# Power_Management.net
KiCad netlist of a schematic drawn in Altium Designer
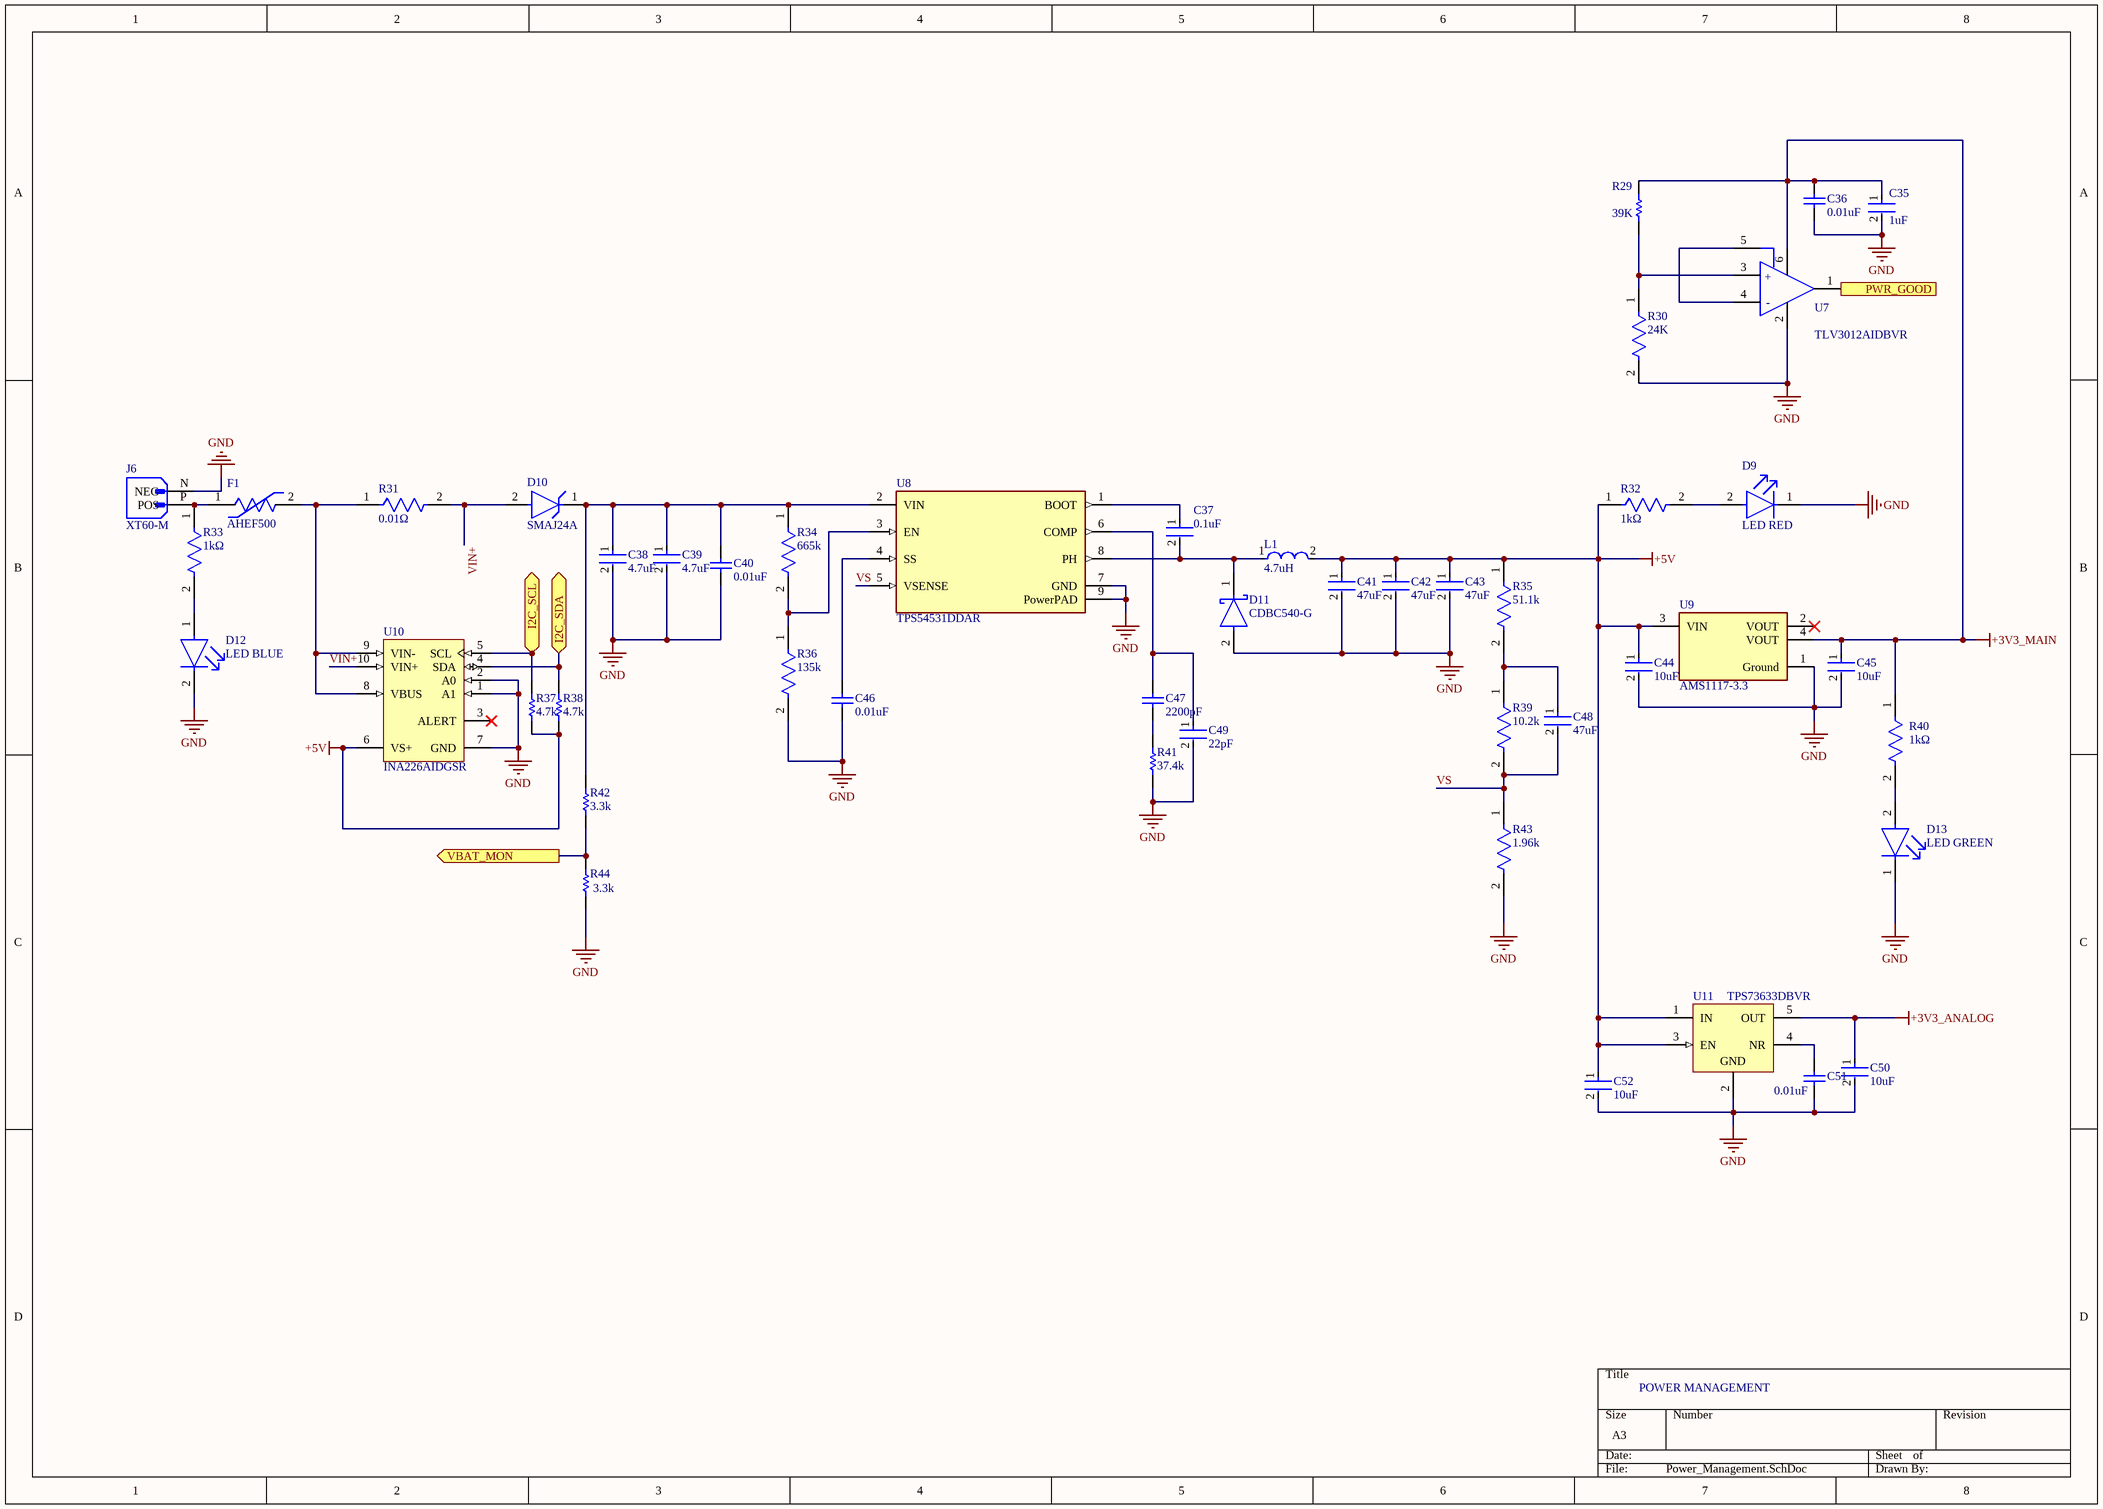
[diagram p0: Power_Management.SchDoc]

(export (version "E")
  (design (tool "Eeschema 10.0.6"))
  (components
    (comp (ref "C35")
      (value "1uF")
      (footprint "FP-GCJ21B-0_3-IPC_B")
      (description "Multilayer Ceramic Capacitors MLCC - SMD/SMT 0805 1uF 10%, 16VDC,  X8L +15/-40%")
      (libsource (lib "Altium Content Vault") (part "02cd4be3c70576c341d710602a673aa"))
    )
    (comp (ref "C36")
      (value "0.01uF")
      (footprint "CAPC1608X87X35NL15T15")
      (fields (field (name "PART NUMBER") "C0603S103J5RACTU") (field (name "MANUFACTURER") "Kemet"))
      (libsource (lib "Altium Content Vault") (part "CAP"))
    )
    (comp (ref "C37")
      (value "0.1uF")
      (footprint "FP-0805B-IPC_C")
      (description "CAP CER 0.1UF 50V X7R 0805")
      (fields (field (name "VOLTAGE") "50V") (field (name "TOLERANCE") "10%"))
      (libsource (lib "Altium Content Vault") (part "02cd4be3c70576c341d710602a673aa"))
    )
    (comp (ref "C38")
      (value "4.7uF")
      (footprint "FP-CC0603-DA-MFG")
      (description "CAP CER 4.7UF 25V X5R 0603")
      (fields
        (field (name "MANUFACTURER") "YAGEO")
        (field (name "MANUFACTURER PART NUMBER") "CC0603KRX5R8BB475")
      )
      (libsource (lib "Altium Content Vault") (part "11868f565c42a9108669ba33697ecf6"))
    )
    (comp (ref "C39")
      (value "4.7uF")
      (footprint "FP-CC0603-DA-MFG")
      (description "CAP CER 4.7UF 25V X5R 0603")
      (fields
        (field (name "MANUFACTURER") "YAGEO")
        (field (name "MANUFACTURER PART NUMBER") "CC0603KRX5R8BB475")
      )
      (libsource (lib "Altium Content Vault") (part "11868f565c42a9108669ba33697ecf6"))
    )
    (comp (ref "C40")
      (value "0.01uF")
      (footprint "CAPC1608X87X35NL15T15")
      (fields (field (name "PART NUMBER") "C0603S103J5RACTU") (field (name "MANUFACTURER") "Kemet"))
      (libsource (lib "Altium Content Vault") (part "CAP"))
    )
    (comp (ref "C41")
      (value "47uF")
      (footprint "FP-0603-L_1_6_0_2-W_0_8_0-MFG")
      (description "Multilayer Ceramic Capacitor 47uF 4V X6S 20% SMD 0603 T/R")
      (libsource (lib "Altium Content Vault") (part "b4654b650e69147ec39a6b967a45e02"))
    )
    (comp (ref "C42")
      (value "47uF")
      (footprint "FP-0603-L_1_6_0_2-W_0_8_0-MFG")
      (description "Multilayer Ceramic Capacitor 47uF 4V X6S 20% SMD 0603 T/R")
      (libsource (lib "Altium Content Vault") (part "b4654b650e69147ec39a6b967a45e02"))
    )
    (comp (ref "C43")
      (value "47uF")
      (footprint "FP-0603-L_1_6_0_2-W_0_8_0-MFG")
      (description "Multilayer Ceramic Capacitor 47uF 4V X6S 20% SMD 0603 T/R")
      (libsource (lib "Altium Content Vault") (part "b4654b650e69147ec39a6b967a45e02"))
    )
    (comp (ref "C44")
      (value "10uF")
      (footprint "FP-C0603C106M8PACTU-MFG")
      (description "CAP CER 10UF 10V X5R 0603")
      (libsource (lib "Altium Content Vault") (part "02cd4be3c70576c341d710602a673aa"))
    )
    (comp (ref "C45")
      (value "10uF")
      (footprint "FP-C0603C106M8PACTU-MFG")
      (description "CAP CER 10UF 10V X5R 0603")
      (libsource (lib "Altium Content Vault") (part "02cd4be3c70576c341d710602a673aa"))
    )
    (comp (ref "C46")
      (value "0.01uF")
      (footprint "CAPC1608X87X35NL15T15")
      (fields (field (name "PART NUMBER") "C0603S103J5RACTU") (field (name "MANUFACTURER") "Kemet"))
      (libsource (lib "Altium Content Vault") (part "CAP"))
    )
    (comp (ref "C47")
      (value "2200pF")
      (footprint "CAPC1608X90X35NL15T15")
      (fields
        (field (name "MANUFACTURER") "AVX Interconnect / Elco")
        (field (name "PART NUMBER") "06035C222KAZ2A")
      )
      (libsource (lib "Altium Content Vault") (part "CAP"))
    )
    (comp (ref "C48")
      (value "47uF")
      (footprint "FP-0603-L_1_6_0_2-W_0_8_0-MFG")
      (description "Multilayer Ceramic Capacitor 47uF 4V X6S 20% SMD 0603 T/R")
      (libsource (lib "Altium Content Vault") (part "b4654b650e69147ec39a6b967a45e02"))
    )
    (comp (ref "C49")
      (value "22pF")
      (footprint "FP-C0603C-CF-MFG")
      (description "CAP CER 22PF 100V C0G/NP0 0603")
      (fields
        (field (name "MANUFACTURER") "KEMET")
        (field (name "MANUFACTURER PART NUMBER") "C0603C220J1GACAUTO")
      )
      (libsource (lib "Altium Content Vault") (part "b4654b650e69147ec39a6b967a45e02"))
    )
    (comp (ref "C50")
      (value "10uF")
      (footprint "FP-C0805C106K8RACAUTO-MFG")
      (description "CAP CER 10UF 10V X7R 0805")
      (fields (field (name "TOLERANCE") "10%"))
      (libsource (lib "Altium Content Vault") (part "b4654b650e69147ec39a6b967a45e02"))
    )
    (comp (ref "C51")
      (value "0.01uF")
      (footprint "CAPC1608X87X35NL15T15")
      (fields (field (name "PART NUMBER") "C0603S103J5RACTU") (field (name "MANUFACTURER") "Kemet"))
      (libsource (lib "Altium Content Vault") (part "CAP"))
    )
    (comp (ref "C52")
      (value "10uF")
      (footprint "FP-C0805C106K8RACAUTO-MFG")
      (description "CAP CER 10UF 10V X7R 0805")
      (fields (field (name "TOLERANCE") "10%"))
      (libsource (lib "Altium Content Vault") (part "b4654b650e69147ec39a6b967a45e02"))
    )
    (comp (ref "D9")
      (value "LED RED")
      (footprint "FP-SML-LXT0805IW-TR-MFG")
      (description "LED RED DIFFUSED SMD")
      (libsource (lib "Altium Content Vault") (part "8706943c75ba83719d021d2fdc84c58"))
    )
    (comp (ref "D10")
      (value "SMAJ24A")
      (footprint "FP-SMAJ-MFG")
      (description "TVS DIODE 24V 38.9V DO214AC")
      (fields
        (field (name "OCTOPART") "https://octopart.com/smaj24a-littelfuse-350003")
        (field (name "MANUFACTURER") "Littelfuse Inc")
      )
      (libsource (lib "Altium Content Vault") (part "f813f71cba58e380607f5dd3caf9714"))
    )
    (comp (ref "D11")
      (value "CDBC540-G")
      (footprint "FP-DO-214AB_SMC-MFG")
      (description "DIODE SCHOTTKY 40V 5A DO214AB")
      (libsource (lib "Altium Content Vault") (part "1d6ec82d83fb6aee721767c19dac4b9"))
    )
    (comp (ref "D12")
      (value "LED BLUE")
      (footprint "FP-SM0805UBWC-MFG")
      (description "LED BLUE CLEAR 0805 SMD")
      (libsource (lib "Altium Content Vault") (part "ab1c01a81903e929fc6c44469aada92"))
    )
    (comp (ref "D13")
      (value "LED GREEN")
      (footprint "FP-LTST-C171GKT-MFG")
      (description "LED GREEN CLEAR CHIP SMD")
      (libsource (lib "Altium Content Vault") (part "8706943c75ba83719d021d2fdc84c58"))
    )
    (comp (ref "F1")
      (value "AHEF500")
      (footprint "FP-AHEF500-MFG")
      (description "PTC RESET FUSE 32V 5A RADIAL")
      (fields
        (field (name "OCTOPART") "https://octopart.com/ahef500-littelfuse-74214520")
        (field (name "MANUFACTURER") "Littelfuse Inc.")
      )
      (libsource (lib "Altium Content Vault") (part "fdf083d5f6389a9a1c4e51137f46658"))
    )
    (comp (ref "J6")
      (value "XT60-M")
      (footprint "AMASS_XT60-M")
      (description "Plug; DC supply; XT60; male; PIN: 2; for cable; soldered; 30A; 500V")
      (fields (field (name "MF") "AMASS"))
      (libsource (lib "XT60-M") (part "XT60-M"))
    )
    (comp (ref "L1")
      (value "4.7uH")
      (footprint "FP-MLZ1608-IPC_A")
      (description "Shielded Multilayer Inductor 4.7uH ±20% 350mA 650mΩ SMD 0603")
      (fields (field (name "TOLERANCE") "20%"))
      (libsource (lib "Altium Content Vault") (part "725321dda6339637d4d059423bc1c3c"))
    )
    (comp (ref "R29")
      (value "39K")
      (footprint "RESC0603(1608)_L")
      (description "39K 0.1W 5% 0603 (1608 Metric)  SMD")
      (fields (field (name "TOLERANCE") "5 %") (field (name "POWER") "0.1 W"))
      (libsource (lib "Altium Content Vault") (part "RES"))
    )
    (comp (ref "R30")
      (value "24K")
      (footprint "FP-CRCW0603-Pe3-MFG")
      (description "RES Thick Film, 24kΩ, 0.5%, 0.1W, 50ppm/°C, 0603")
      (fields (field (name "TOLERANCE") "0.5%"))
      (libsource (lib "Altium Content Vault") (part "1029c3af85768c4190bb7ad29bc67b5"))
    )
    (comp (ref "R31")
      (value "0.01Ω")
      (footprint "FP-GMR320-MFG")
      (description "RES 10M OHM 1% 10W 2817")
      (libsource (lib "Altium Content Vault") (part "1029c3af85768c4190bb7ad29bc67b5"))
    )
    (comp (ref "R32")
      (value "1kΩ")
      (footprint "FP-RNCF0603-MFG")
      (description "RES 1K OHM, 0.01%, 2 PPM, 0.1W,")
      (libsource (lib "Altium Content Vault") (part "1029c3af85768c4190bb7ad29bc67b5"))
    )
    (comp (ref "R33")
      (value "1kΩ")
      (footprint "FP-RNCF0603-MFG")
      (description "RES 1K OHM, 0.01%, 2 PPM, 0.1W,")
      (libsource (lib "Altium Content Vault") (part "1029c3af85768c4190bb7ad29bc67b5"))
    )
    (comp (ref "R34")
      (value "665k")
      (footprint "FP-CRCW0603-HPe3-IPC_B")
      (description "RES Thick Film, 665kΩ, 1%, 0.33W, 100ppm/°C, 0603")
      (fields (field (name "TOLERANCE") "1%"))
      (libsource (lib "Altium Content Vault") (part "1029c3af85768c4190bb7ad29bc67b5"))
    )
    (comp (ref "R35")
      (value "51.1k")
      (footprint "FP-CRCW0603-e3-IPC_B")
      (description "RES Thick Film, 511kΩ, 1%, 0.1W, 100ppm/°C, 0603")
      (fields (field (name "TOLERANCE") "1%"))
      (libsource (lib "Altium Content Vault") (part "1029c3af85768c4190bb7ad29bc67b5"))
    )
    (comp (ref "R36")
      (value "135k")
      (footprint "FP-CRCW0603-e3-IPC_C")
      (description "RES Thick Film, 130kΩ, 5%, 0.1W, 200ppm/°C, 0603")
      (fields (field (name "TOLERANCE") "5%"))
      (libsource (lib "Altium Content Vault") (part "1029c3af85768c4190bb7ad29bc67b5"))
    )
    (comp (ref "R37")
      (value "4.7k")
      (footprint "RESC3225X75X50ML15T25")
      (fields (field (name "MANUFACTURER") "Vishay Dale") (field (name "PART NUMBER") "TNPW12104K70BETA"))
      (libsource (lib "Altium Content Vault") (part "RES"))
    )
    (comp (ref "R38")
      (value "4.7k")
      (footprint "RESC3225X75X50ML15T25")
      (fields (field (name "MANUFACTURER") "Vishay Dale") (field (name "PART NUMBER") "TNPW12104K70BETA"))
      (libsource (lib "Altium Content Vault") (part "RES"))
    )
    (comp (ref "R39")
      (value "10.2k")
      (footprint "FP-AC0603-IPC_B")
      (description "RES 2kΩ 1.00% 0.1W 0603")
      (fields (field (name "TOLERANCE") "1%"))
      (libsource (lib "Altium Content Vault") (part "1029c3af85768c4190bb7ad29bc67b5"))
    )
    (comp (ref "R40")
      (value "1kΩ")
      (footprint "FP-RNCF0603-MFG")
      (description "RES 1K OHM, 0.01%, 2 PPM, 0.1W,")
      (libsource (lib "Altium Content Vault") (part "1029c3af85768c4190bb7ad29bc67b5"))
    )
    (comp (ref "R41")
      (value "37.4k")
      (footprint "RESC1608X55X25NL10T15")
      (fields (field (name "PART NUMBER") "RC0603FR-07374KL") (field (name "MANUFACTURER") "Yageo"))
      (libsource (lib "Altium Content Vault") (part "RES"))
    )
    (comp (ref "R42")
      (value "3.3k")
      (footprint "RESC1812(4532)_L")
      (description "10K 0.75W 1% 1812 (4532 Metric)  SMD")
      (fields (field (name "POWER") "0.75 W") (field (name "TOLERANCE") "1 %"))
      (libsource (lib "Altium Content Vault") (part "RES"))
    )
    (comp (ref "R43")
      (value "1.96k")
      (footprint "FP-CRCW0603-HPe3-IPC_B")
      (description "RES Thick Film, 1.96kΩ, 1%, 0.33W, 100ppm/°C, 0603")
      (fields (field (name "TOLERANCE") "1%"))
      (libsource (lib "Altium Content Vault") (part "1029c3af85768c4190bb7ad29bc67b5"))
    )
    (comp (ref "R44")
      (value "3.3k")
      (footprint "RESC2512(6432)_M")
      (description "3K3 1W 1% 2512 (6432 Metric)  SMD")
      (fields (field (name "TOLERANCE") "1 %") (field (name "POWER") "1 W"))
      (libsource (lib "Altium Content Vault") (part "RES"))
    )
    (comp (ref "U7")
      (value "TLV3012AIDBVR")
      (footprint "FP-DBV0006A-IPC_B")
      (description "IC COMPARATOR 1.8V W/REF SOT23-6")
      (libsource (lib "Altium Content Vault") (part "c4a04de7fcb83ef995881f343e5bdea"))
    )
    (comp (ref "U8")
      (value "TPS54531DDAR")
      (footprint "FP-DDA0008E-MFG")
      (description "IC REG BUCK ADJUSTABLE 5A 8SOPWR")
      (libsource (lib "Altium Content Vault") (part "0ba9c67d8848e7a3c062535a516a02c"))
    )
    (comp (ref "U9")
      (value "AMS1117-3.3")
      (footprint "FP-AMS1117-IPC_C")
      (description "LDO Voltage Regulators 1A, 3.3V")
      (fields
        (field (name "OCTOPART") "https://octopart.com/ams1117-3.3-advanced+monolithic+systems-25899300")
        (field (name "MANUFACTURER") "Advanced Monolithic Systems")
      )
      (libsource (lib "Altium Content Vault") (part "8bdbb5f8e77002000e30dd2845d0354"))
    )
    (comp (ref "U10")
      (value "INA226AIDGSR")
      (footprint "DGS0010A_L")
      (libsource (lib "Altium Content Vault") (part "TI-INA226DGS10"))
    )
    (comp (ref "U11")
      (value "TPS73633DBVR")
      (footprint "DBV0005A_L")
      (fields (field (name "MANUFACTURER") "Texas Instruments"))
      (libsource (lib "Altium Content Vault") (part "TI-TPS79NXX-YYSOT5"))
    )
  )
  (nets
    (net (code "1") (name "+3V3_ANALOG") (class "Default")
      (node (ref "C50") (pin "1") (pinfunction "1_1") (pintype "passive"))
      (node (ref "U11") (pin "5") (pinfunction "OUT_5") (pintype "power_in"))
    )
    (net (code "2") (name "+3V3_MAIN") (class "Default")
      (node (ref "C35") (pin "1") (pinfunction "1_1") (pintype "passive"))
      (node (ref "C36") (pin "2") (pinfunction "2_2") (pintype "passive"))
      (node (ref "C45") (pin "1") (pinfunction "1_1") (pintype "passive"))
      (node (ref "R29") (pin "2") (pinfunction "2_2") (pintype "passive"))
      (node (ref "R40") (pin "1") (pinfunction "1_1") (pintype "passive"))
      (node (ref "U7") (pin "6") (pinfunction "V+_6") (pintype "power_in"))
      (node (ref "U9") (pin "4") (pinfunction "VOUT_4") (pintype "passive"))
    )
    (net (code "3") (name "+5V") (class "Default")
      (node (ref "C41") (pin "1") (pinfunction "1_1") (pintype "passive"))
      (node (ref "C42") (pin "1") (pinfunction "1_1") (pintype "passive"))
      (node (ref "C43") (pin "1") (pinfunction "1_1") (pintype "passive"))
      (node (ref "C44") (pin "1") (pinfunction "1_1") (pintype "passive"))
      (node (ref "C52") (pin "1") (pinfunction "1_1") (pintype "passive"))
      (node (ref "L1") (pin "2") (pinfunction "2_2") (pintype "passive"))
      (node (ref "R32") (pin "1") (pinfunction "1_1") (pintype "passive"))
      (node (ref "R35") (pin "1") (pinfunction "1_1") (pintype "passive"))
      (node (ref "R37") (pin "1") (pinfunction "1_1") (pintype "passive"))
      (node (ref "R38") (pin "1") (pinfunction "1_1") (pintype "passive"))
      (node (ref "U10") (pin "6") (pinfunction "VS+_6") (pintype "power_in"))
      (node (ref "U11") (pin "1") (pinfunction "IN_1") (pintype "power_in"))
      (node (ref "U11") (pin "3") (pinfunction "EN_3") (pintype "input"))
      (node (ref "U9") (pin "3") (pinfunction "VIN_3") (pintype "power_in"))
    )
    (net (code "4") (name "/I2C_SCL") (class "Default")
      (node (ref "R37") (pin "2") (pinfunction "2_2") (pintype "passive"))
      (node (ref "U10") (pin "5") (pinfunction "SCL_5") (pintype "input"))
    )
    (net (code "5") (name "/I2C_SDA") (class "Default")
      (node (ref "R38") (pin "2") (pinfunction "2_2") (pintype "passive"))
      (node (ref "U10") (pin "4") (pinfunction "SDA_4") (pintype "bidirectional"))
    )
    (net (code "6") (name "/PWR_GOOD") (class "Default")
      (node (ref "U7") (pin "1") (pinfunction "OUT_1") (pintype "passive"))
    )
    (net (code "7") (name "/VBAT_MON") (class "Default")
      (node (ref "R42") (pin "1") (pinfunction "1_1") (pintype "passive"))
      (node (ref "R44") (pin "2") (pinfunction "2_2") (pintype "passive"))
    )
    (net (code "8") (name "/VIN+") (class "Default")
      (node (ref "D10") (pin "2") (pinfunction "A_2") (pintype "passive"))
      (node (ref "R31") (pin "2") (pinfunction "2_2") (pintype "passive"))
      (node (ref "U10") (pin "10") (pinfunction "VIN+_10") (pintype "input"))
    )
    (net (code "9") (name "/VS") (class "Default")
      (node (ref "C48") (pin "2") (pinfunction "2_2") (pintype "passive"))
      (node (ref "R39") (pin "2") (pinfunction "2_2") (pintype "passive"))
      (node (ref "R43") (pin "1") (pinfunction "1_1") (pintype "passive"))
      (node (ref "U8") (pin "5") (pinfunction "VSENSE_5") (pintype "input"))
    )
    (net (code "10") (name "GND") (class "Default")
      (node (ref "C35") (pin "2") (pinfunction "2_2") (pintype "passive"))
      (node (ref "C36") (pin "1") (pinfunction "1_1") (pintype "passive"))
      (node (ref "C38") (pin "2") (pinfunction "2_2") (pintype "passive"))
      (node (ref "C39") (pin "2") (pinfunction "2_2") (pintype "passive"))
      (node (ref "C40") (pin "1") (pinfunction "1_1") (pintype "passive"))
      (node (ref "C41") (pin "2") (pinfunction "2_2") (pintype "passive"))
      (node (ref "C42") (pin "2") (pinfunction "2_2") (pintype "passive"))
      (node (ref "C43") (pin "2") (pinfunction "2_2") (pintype "passive"))
      (node (ref "C44") (pin "2") (pinfunction "2_2") (pintype "passive"))
      (node (ref "C45") (pin "2") (pinfunction "2_2") (pintype "passive"))
      (node (ref "C46") (pin "1") (pinfunction "1_1") (pintype "passive"))
      (node (ref "C49") (pin "2") (pinfunction "2_2") (pintype "passive"))
      (node (ref "C50") (pin "2") (pinfunction "2_2") (pintype "passive"))
      (node (ref "C51") (pin "1") (pinfunction "1_1") (pintype "passive"))
      (node (ref "C52") (pin "2") (pinfunction "2_2") (pintype "passive"))
      (node (ref "D11") (pin "2") (pinfunction "A_2") (pintype "passive"))
      (node (ref "D12") (pin "2") (pinfunction "C_2") (pintype "passive"))
      (node (ref "D13") (pin "1") (pinfunction "C_1") (pintype "passive"))
      (node (ref "D9") (pin "1") (pinfunction "C_1") (pintype "passive"))
      (node (ref "J6") (pin "N") (pinfunction "NEG_N") (pintype "passive"))
      (node (ref "R30") (pin "2") (pinfunction "2_2") (pintype "passive"))
      (node (ref "R36") (pin "2") (pinfunction "2_2") (pintype "passive"))
      (node (ref "R41") (pin "1") (pinfunction "1_1") (pintype "passive"))
      (node (ref "R43") (pin "2") (pinfunction "2_2") (pintype "passive"))
      (node (ref "R44") (pin "1") (pinfunction "1_1") (pintype "passive"))
      (node (ref "U10") (pin "1") (pinfunction "A1_1") (pintype "input"))
      (node (ref "U10") (pin "2") (pinfunction "A0_2") (pintype "input"))
      (node (ref "U10") (pin "7") (pinfunction "GND_7") (pintype "power_in"))
      (node (ref "U11") (pin "2") (pinfunction "GND_2") (pintype "power_in"))
      (node (ref "U7") (pin "2") (pinfunction "V-_2") (pintype "power_in"))
      (node (ref "U8") (pin "7") (pinfunction "GND_7") (pintype "power_in"))
      (node (ref "U8") (pin "9") (pinfunction "PowerPAD_9") (pintype "power_in"))
      (node (ref "U9") (pin "1") (pinfunction "Ground_1") (pintype "power_in"))
    )
    (net (code "11") (name "Net-(C47-Pad1)") (class "Default")
      (node (ref "C47") (pin "1") (pinfunction "1_1") (pintype "passive"))
      (node (ref "R41") (pin "2") (pinfunction "2_2") (pintype "passive"))
    )
    (net (code "12") (name "Net-(C48-Pad1)") (class "Default")
      (node (ref "C48") (pin "1") (pinfunction "1_1") (pintype "passive"))
      (node (ref "R35") (pin "2") (pinfunction "2_2") (pintype "passive"))
      (node (ref "R39") (pin "1") (pinfunction "1_1") (pintype "passive"))
    )
    (net (code "13") (name "Net-(D9-A)") (class "Default")
      (node (ref "D9") (pin "2") (pinfunction "A_2") (pintype "passive"))
      (node (ref "R32") (pin "2") (pinfunction "2_2") (pintype "passive"))
    )
    (net (code "14") (name "Net-(D10-C)") (class "Default")
      (node (ref "C38") (pin "1") (pinfunction "1_1") (pintype "passive"))
      (node (ref "C39") (pin "1") (pinfunction "1_1") (pintype "passive"))
      (node (ref "C40") (pin "2") (pinfunction "2_2") (pintype "passive"))
      (node (ref "D10") (pin "1") (pinfunction "C_1") (pintype "passive"))
      (node (ref "R34") (pin "1") (pinfunction "1_1") (pintype "passive"))
      (node (ref "R42") (pin "2") (pinfunction "2_2") (pintype "passive"))
      (node (ref "U8") (pin "2") (pinfunction "VIN_2") (pintype "power_in"))
    )
    (net (code "15") (name "Net-(D11-C)") (class "Default")
      (node (ref "C37") (pin "2") (pinfunction "2_2") (pintype "passive"))
      (node (ref "D11") (pin "1") (pinfunction "C_1") (pintype "passive"))
      (node (ref "L1") (pin "1") (pinfunction "1_1") (pintype "passive"))
      (node (ref "U8") (pin "8") (pinfunction "PH_8") (pintype "output"))
    )
    (net (code "16") (name "Net-(D12-A)") (class "Default")
      (node (ref "D12") (pin "1") (pinfunction "A_1") (pintype "passive"))
      (node (ref "R33") (pin "2") (pinfunction "2_2") (pintype "passive"))
    )
    (net (code "17") (name "Net-(D13-A)") (class "Default")
      (node (ref "D13") (pin "2") (pinfunction "A_2") (pintype "passive"))
      (node (ref "R40") (pin "2") (pinfunction "2_2") (pintype "passive"))
    )
    (net (code "18") (name "Net-(J6-POS)") (class "Default")
      (node (ref "F1") (pin "1") (pinfunction "1_1") (pintype "passive"))
      (node (ref "J6") (pin "P") (pinfunction "POS_P") (pintype "passive"))
      (node (ref "R33") (pin "1") (pinfunction "1_1") (pintype "passive"))
    )
    (net (code "19") (name "Net-(U7-IN+)") (class "Default")
      (node (ref "R29") (pin "1") (pinfunction "1_1") (pintype "passive"))
      (node (ref "R30") (pin "1") (pinfunction "1_1") (pintype "passive"))
      (node (ref "U7") (pin "3") (pinfunction "IN+_3") (pintype "tri_state"))
    )
    (net (code "20") (name "Net-(U7-IN-)") (class "Default")
      (node (ref "U7") (pin "4") (pinfunction "IN-_4") (pintype "tri_state"))
      (node (ref "U7") (pin "5") (pinfunction "REF_5") (pintype "passive"))
    )
    (net (code "21") (name "Net-(U8-BOOT)") (class "Default")
      (node (ref "C37") (pin "1") (pinfunction "1_1") (pintype "passive"))
      (node (ref "U8") (pin "1") (pinfunction "BOOT_1") (pintype "output"))
    )
    (net (code "22") (name "Net-(U8-COMP)") (class "Default")
      (node (ref "C47") (pin "2") (pinfunction "2_2") (pintype "passive"))
      (node (ref "C49") (pin "1") (pinfunction "1_1") (pintype "passive"))
      (node (ref "U8") (pin "6") (pinfunction "COMP_6") (pintype "output"))
    )
    (net (code "23") (name "Net-(U8-EN)") (class "Default")
      (node (ref "R34") (pin "2") (pinfunction "2_2") (pintype "passive"))
      (node (ref "R36") (pin "1") (pinfunction "1_1") (pintype "passive"))
      (node (ref "U8") (pin "3") (pinfunction "EN_3") (pintype "input"))
    )
    (net (code "24") (name "Net-(U8-SS)") (class "Default")
      (node (ref "C46") (pin "2") (pinfunction "2_2") (pintype "passive"))
      (node (ref "U8") (pin "4") (pinfunction "SS_4") (pintype "input"))
    )
    (net (code "25") (name "Net-(U10-VBUS)") (class "Default")
      (node (ref "F1") (pin "2") (pinfunction "2_2") (pintype "passive"))
      (node (ref "R31") (pin "1") (pinfunction "1_1") (pintype "passive"))
      (node (ref "U10") (pin "8") (pinfunction "VBUS_8") (pintype "input"))
      (node (ref "U10") (pin "9") (pinfunction "VIN-_9") (pintype "input"))
    )
    (net (code "26") (name "Net-(U11-NR)") (class "Default")
      (node (ref "C51") (pin "2") (pinfunction "2_2") (pintype "passive"))
      (node (ref "U11") (pin "4") (pinfunction "NR_4") (pintype "passive"))
    )
    (net (code "27") (name "unconnected-(U9-VOUT-Pad2)") (class "Default")
      (node (ref "U9") (pin "2") (pinfunction "VOUT_2") (pintype "passive+no_connect"))
    )
    (net (code "28") (name "unconnected-(U10-ALERT-Pad3)") (class "Default")
      (node (ref "U10") (pin "3") (pinfunction "ALERT_3") (pintype "open_collector+no_connect"))
    )
  )
)
